# MCU_USB.net
KiCad netlist of a schematic drawn in Altium Designer
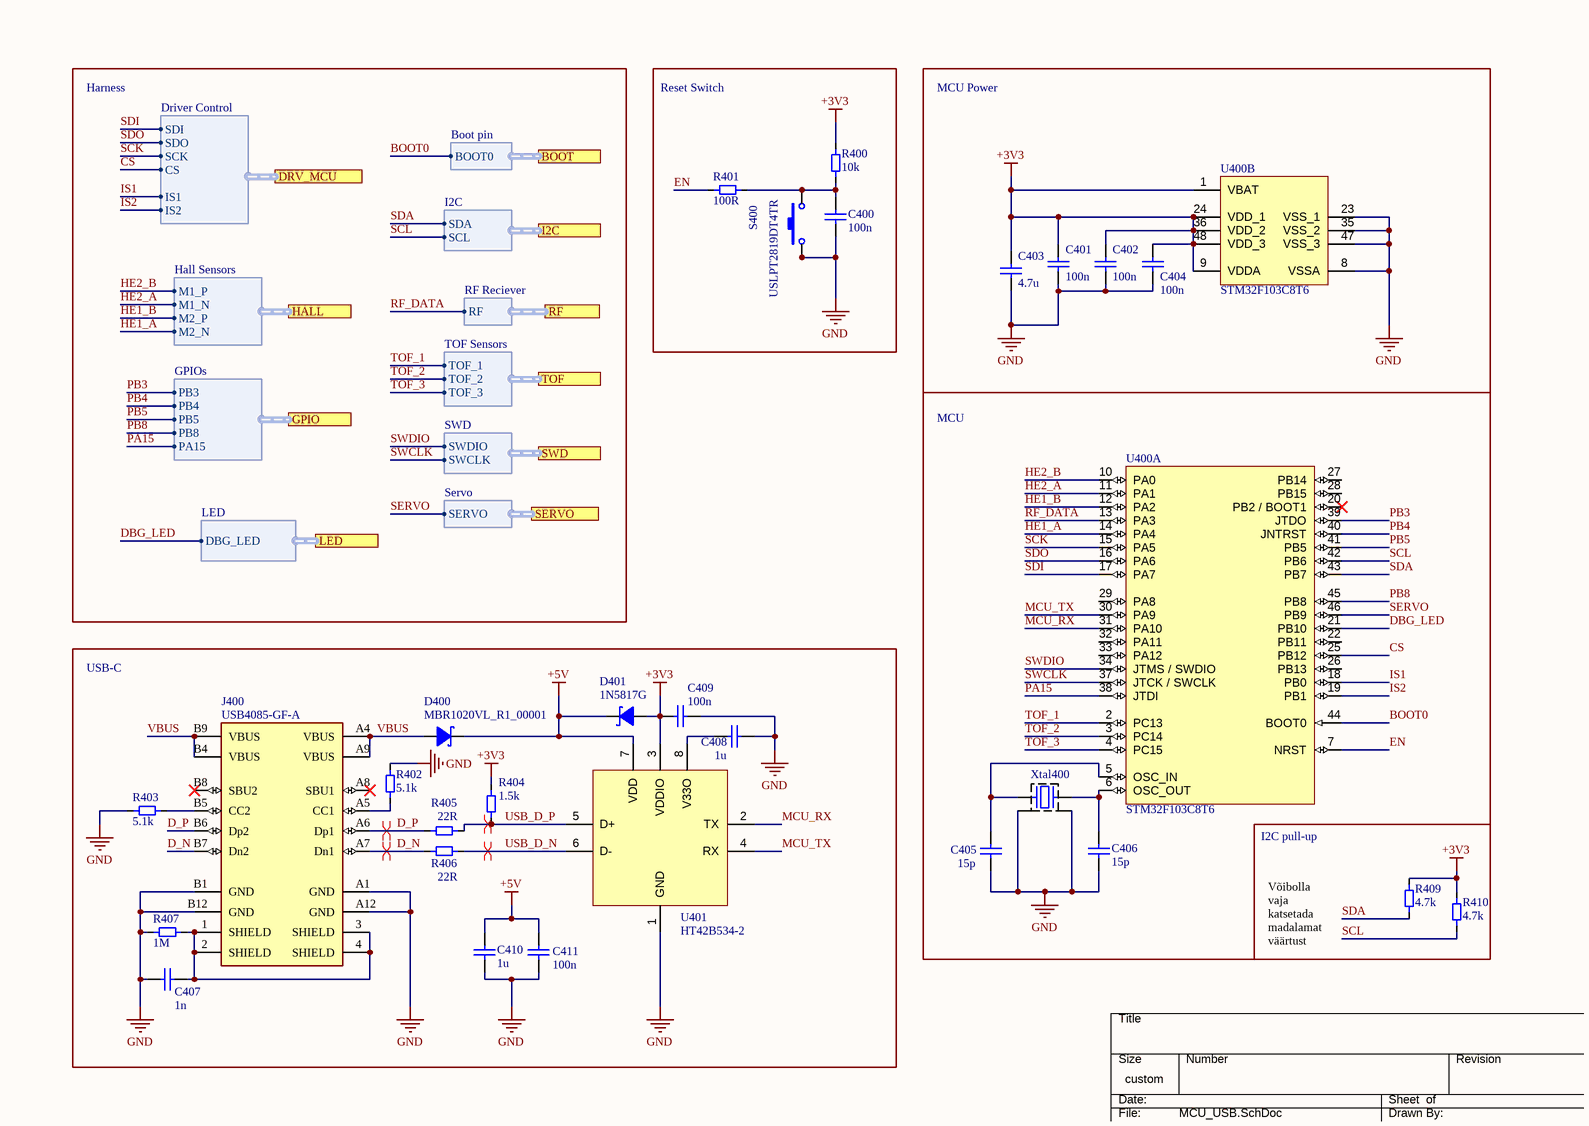
[diagram p0: MCU_USB.SchDoc]

(export (version "E")
  (design (tool "Eeschema 10.0.6"))
  (components
    (comp (ref "C400")
      (value "100n")
      (footprint "MLCC_0603_M")
      (description "MLCC, 0603, 100n, 10%, 50V, X7R")
      (fields (field (name "VOLTAGE") "50V") (field (name "TOLERANCE") "10%"))
      (libsource (lib "Krakul Vault") (part "CAPACITOR_NONPOL_IEC"))
    )
    (comp (ref "C401")
      (value "100n")
      (footprint "MLCC_0603_M")
      (description "MLCC, 0603, 100n, 10%, 50V, X7R")
      (fields (field (name "VOLTAGE") "50V") (field (name "TOLERANCE") "10%"))
      (libsource (lib "Krakul Vault") (part "CAPACITOR_NONPOL_IEC"))
    )
    (comp (ref "C402")
      (value "100n")
      (footprint "MLCC_0603_M")
      (description "MLCC, 0603, 100n, 10%, 50V, X7R")
      (fields (field (name "VOLTAGE") "50V") (field (name "TOLERANCE") "10%"))
      (libsource (lib "Krakul Vault") (part "CAPACITOR_NONPOL_IEC"))
    )
    (comp (ref "C403")
      (value "4.7u")
      (footprint "MLCC_0805_M")
      (description "MLCC, 0805, 4.7u, 20%, 50V, X5R")
      (fields (field (name "MANUFACTURER") "Any") (field (name "VOLTAGE") "50V"))
      (libsource (lib "Krakul Vault") (part "CAPACITOR_NONPOL_IEC"))
    )
    (comp (ref "C404")
      (value "100n")
      (footprint "MLCC_0603_M")
      (description "MLCC, 0603, 100n, 10%, 50V, X7R")
      (fields (field (name "VOLTAGE") "50V") (field (name "TOLERANCE") "10%"))
      (libsource (lib "Krakul Vault") (part "CAPACITOR_NONPOL_IEC"))
    )
    (comp (ref "C405")
      (value "15p")
      (footprint "MLCC_0402_M")
      (description "MLCC, 0402, 15p, 10%, 25V, C0G/NP0")
      (fields (field (name "MANUFACTURER") "Any") (field (name "TOLERANCE") "10%"))
      (libsource (lib "Krakul Vault") (part "CAPACITOR_NONPOL_IEC"))
    )
    (comp (ref "C406")
      (value "15p")
      (footprint "MLCC_0402_M")
      (description "MLCC, 0402, 15p, 10%, 25V, C0G/NP0")
      (fields (field (name "MANUFACTURER") "Any") (field (name "TOLERANCE") "10%"))
      (libsource (lib "Krakul Vault") (part "CAPACITOR_NONPOL_IEC"))
    )
    (comp (ref "C407")
      (value "1n")
      (footprint "MLCC_0603_M")
      (description "MLCC, 0603, 1n, 10%, 50V, X5R")
      (fields (field (name "MANUFACTURER") "Any") (field (name "TOLERANCE") "10%"))
      (libsource (lib "Krakul Vault") (part "CAPACITOR_NONPOL_IEC"))
    )
    (comp (ref "C408")
      (value "1u")
      (footprint "MLCC_0603_M")
      (description "MLCC, 0603, 1u, 10%, 50V, X5R")
      (fields (field (name "MANUFACTURER") "Any") (field (name "VOLTAGE") "50V"))
      (libsource (lib "Krakul Vault") (part "CAPACITOR_NONPOL_IEC"))
    )
    (comp (ref "C409")
      (value "100n")
      (footprint "MLCC_0603_M")
      (description "MLCC, 0603, 100n, 10%, 50V, X7R")
      (fields (field (name "VOLTAGE") "50V") (field (name "TOLERANCE") "10%"))
      (libsource (lib "Krakul Vault") (part "CAPACITOR_NONPOL_IEC"))
    )
    (comp (ref "C410")
      (value "1u")
      (footprint "MLCC_0603_M")
      (description "MLCC, 0603, 1u, 10%, 50V, X5R")
      (fields (field (name "MANUFACTURER") "Any") (field (name "VOLTAGE") "50V"))
      (libsource (lib "Krakul Vault") (part "CAPACITOR_NONPOL_IEC"))
    )
    (comp (ref "C411")
      (value "100n")
      (footprint "MLCC_0603_M")
      (description "MLCC, 0603, 100n, 10%, 50V, X7R")
      (fields (field (name "VOLTAGE") "50V") (field (name "TOLERANCE") "10%"))
      (libsource (lib "Krakul Vault") (part "CAPACITOR_NONPOL_IEC"))
    )
    (comp (ref "D400")
      (value "MBR1020VL_R1_00001")
      (footprint "FP-MBR1020VL_R1_00001-MFG")
      (description "Rectifier Diode, Schottky, 1 Phase, 1 Element, 1A, 20V V(RRM), Silicon")
      (fields (field (name "MANUFACTURER") "Panjit"))
      (libsource (lib "Krakul Vault") (part "Schottky generic 2 pins"))
    )
    (comp (ref "D401")
      (value "1N5817G")
      (footprint "SOD-323 based on 1N5817WS")
      (description "Rectifier Diode, Schottky, 1 Phase, 1 Element, 1A, 20V V(RRM), Silicon, DO-204AL")
      (fields (field (name "MANUFACTURER") "TWGMC / onsemi") (field (name "PART NUMBER") "1N5817WS"))
      (libsource (lib "Krakul Vault") (part "Schottky generic 2 pins"))
    )
    (comp (ref "J400")
      (value "USB4085-GF-A")
      (footprint "FP-USB4085-GF-A-MFG")
      (description "USB Connector, 16 Contact(s), Female, Right Angle, Solder Terminal, Locking, Receptacle")
      (fields (field (name "MANUFACTURER") "GCT") (field (name "PART NUMBER") "USB4800-03-A"))
      (libsource (lib "Krakul Vault") (part "USB4085-GF-A"))
    )
    (comp (ref "R400")
      (value "10k")
      (footprint "Resistor_0603_M")
      (description "Resistor, 0603, 10k, 1%, 1/10W")
      (fields (field (name "MANUFACTURER") "Any") (field (name "TOLERANCE") "1%"))
      (libsource (lib "Krakul Vault") (part "RESISTOR_GENERIC_IEC"))
    )
    (comp (ref "R401")
      (value "100R")
      (footprint "Resistor_0603_M")
      (description "Resistor, 0603, 100R, 1%, 1/10W")
      (fields (field (name "POWER") "100mW") (field (name "MANUFACTURER") "Any"))
      (libsource (lib "Krakul Vault") (part "RESISTOR_GENERIC_IEC"))
    )
    (comp (ref "R402")
      (value "5.1k")
      (footprint "Resistor_0603_M")
      (description "Resistor, 0603, 5.1k, 1%, 1/10W")
      (fields (field (name "POWER") "100mW") (field (name "MANUFACTURER") "Any"))
      (libsource (lib "Krakul Vault") (part "RESISTOR_GENERIC_IEC"))
    )
    (comp (ref "R403")
      (value "5.1k")
      (footprint "Resistor_0603_M")
      (description "Resistor, 0603, 5.1k, 1%, 1/10W")
      (fields (field (name "POWER") "100mW") (field (name "MANUFACTURER") "Any"))
      (libsource (lib "Krakul Vault") (part "RESISTOR_GENERIC_IEC"))
    )
    (comp (ref "R404")
      (value "1.5k")
      (footprint "Resistor_0603_M")
      (description "Resistor, 0603, 1.5k, 1%, 1/10W")
      (fields (field (name "MANUFACTURER") "Any") (field (name "POWER") "100mW"))
      (libsource (lib "Krakul Vault") (part "RESISTOR_GENERIC_IEC"))
    )
    (comp (ref "R405")
      (value "22R")
      (footprint "Resistor_0603_M")
      (description "Resistor, 0603, 22R, 1%, 1/10W")
      (fields (field (name "TOLERANCE") "1%") (field (name "MANUFACTURER") "Any"))
      (libsource (lib "Krakul Vault") (part "RESISTOR_GENERIC_IEC"))
    )
    (comp (ref "R406")
      (value "22R")
      (footprint "Resistor_0603_M")
      (description "Resistor, 0603, 22R, 1%, 1/10W")
      (fields (field (name "TOLERANCE") "1%") (field (name "MANUFACTURER") "Any"))
      (libsource (lib "Krakul Vault") (part "RESISTOR_GENERIC_IEC"))
    )
    (comp (ref "R407")
      (value "1M")
      (footprint "Resistor_1206_M")
      (description "Resistor, 1206, 1M, 1%, 1/4W")
      (fields (field (name "MANUFACTURER") "Any"))
      (libsource (lib "Krakul Vault") (part "RESISTOR_GENERIC_IEC"))
    )
    (comp (ref "R409")
      (value "4.7k")
      (footprint "Resistor_0603_M")
      (description "Resistor, 0603, 4.7k, 1%, 1/10W")
      (fields (field (name "MANUFACTURER") "Any") (field (name "POWER") "100mW"))
      (libsource (lib "Krakul Vault") (part "RESISTOR_GENERIC_IEC"))
    )
    (comp (ref "R410")
      (value "4.7k")
      (footprint "Resistor_0603_M")
      (description "Resistor, 0603, 4.7k, 1%, 1/10W")
      (fields (field (name "MANUFACTURER") "Any") (field (name "POWER") "100mW"))
      (libsource (lib "Krakul Vault") (part "RESISTOR_GENERIC_IEC"))
    )
    (comp (ref "S400")
      (value "USLPT2819DT4TR")
      (footprint "USLPT2819DT4TR-Footprint-1")
      (description "Keypad Switch, SPST, 0.05A, 1.96N, Solder Terminal, Panel Mount")
      (fields (field (name "MANUFACTURER") "TE Connectivity ALCOSWITCH Switches"))
      (libsource (lib "Krakul Vault") (part "Copy of Switch 4-pin"))
    )
    (comp (ref "U400")
      (value "STM32F103C8T6")
      (footprint "STM-LQFP48_M")
      (description "MCU 32-bit STM32F1 ARM Cortex M3 RISC 64KB Flash 2.5V/3.3V 48-Pin LQFP Tray")
      (fields (field (name "MANUFACTURER") "STMicroelectronics"))
      (libsource (lib "") (part "MC-ARM-STM32F103X4_6-SQ48_1"))
    )
    (comp (ref "U401")
      (value "HT42B534-2")
      (footprint "SOP-8 150mil")
      (description "USB to UART 3Mbps USB 2.0 SOP-8 Interface Controllers RoHS")
      (fields (field (name "MANUFACTURER") "HOLTEK"))
      (libsource (lib "Krakul Vault") (part "HT42B534-2"))
    )
    (comp (ref "Xtal400")
      (value "ABM11-16.000MHZ-12-N1G-T")
      (footprint "FP-ABM11-MFG")
      (description "Crystal 16MHz ±10ppm (Tol) ±15ppm (Stability) 12pF FUND 150Ohm 4-Pin Ultra Mini-CSMD T/R")
      (fields (field (name "MANUFACTURER") "Abracon LLC") (field (name "TOLERANCE") "0.001%"))
      (libsource (lib "Krakul Vault") (part "Crystal 4 pins"))
    )
  )
  (nets
    (net (code "15") (name "+3V3") (class "Default")
      (node (ref "C401") (pin "1") (pinfunction "1_1") (pintype "passive"))
      (node (ref "C402") (pin "1") (pinfunction "1_1") (pintype "passive"))
      (node (ref "C403") (pin "2") (pinfunction "2_2") (pintype "passive"))
      (node (ref "C404") (pin "1") (pinfunction "1_1") (pintype "passive"))
      (node (ref "C409") (pin "1") (pinfunction "1_1") (pintype "passive"))
      (node (ref "D401") (pin "2") (pinfunction "A_2") (pintype "passive"))
      (node (ref "R400") (pin "2") (pinfunction "2_2") (pintype "passive"))
      (node (ref "R404") (pin "2") (pinfunction "2_2") (pintype "passive"))
      (node (ref "R409") (pin "2") (pinfunction "2_2") (pintype "passive"))
      (node (ref "R410") (pin "2") (pinfunction "2_2") (pintype "passive"))
      (node (ref "U400") (pin "1") (pinfunction "VBAT_1") (pintype "power_in"))
      (node (ref "U400") (pin "24") (pinfunction "VDD_1_24") (pintype "power_in"))
      (node (ref "U400") (pin "36") (pinfunction "VDD_2_36") (pintype "power_in"))
      (node (ref "U400") (pin "48") (pinfunction "VDD_3_48") (pintype "power_in"))
      (node (ref "U400") (pin "9") (pinfunction "VDDA_9") (pintype "power_in"))
      (node (ref "U401") (pin "3") (pinfunction "VDDIO_3") (pintype "passive"))
    )
    (net (code "16") (name "+5V") (class "Default")
      (node (ref "C410") (pin "2") (pinfunction "2_2") (pintype "passive"))
      (node (ref "C411") (pin "1") (pinfunction "1_1") (pintype "passive"))
      (node (ref "D400") (pin "1") (pinfunction "C_1") (pintype "passive"))
      (node (ref "D401") (pin "1") (pinfunction "C_1") (pintype "passive"))
      (node (ref "U401") (pin "7") (pinfunction "VDD_7") (pintype "passive"))
    )
    (net (code "17") (name "/BOOT0") (class "Default")
      (node (ref "U400") (pin "44") (pinfunction "BOOT0_44") (pintype "input"))
    )
    (net (code "18") (name "/CS") (class "Default")
      (node (ref "U400") (pin "25") (pinfunction "PB12_25") (pintype "bidirectional"))
    )
    (net (code "19") (name "/DBG_LED") (class "Default")
      (node (ref "U400") (pin "21") (pinfunction "PB10_21") (pintype "bidirectional"))
    )
    (net (code "20") (name "/D_N") (class "Default")
      (node (ref "J400") (pin "A7") (pinfunction "Dn1_A7") (pintype "bidirectional"))
      (node (ref "J400") (pin "B7") (pinfunction "Dn2_B7") (pintype "bidirectional"))
      (node (ref "R406") (pin "1") (pinfunction "1_1") (pintype "passive"))
    )
    (net (code "21") (name "/D_P") (class "Default")
      (node (ref "J400") (pin "A6") (pinfunction "Dp1_A6") (pintype "bidirectional"))
      (node (ref "J400") (pin "B6") (pinfunction "Dp2_B6") (pintype "bidirectional"))
      (node (ref "R405") (pin "1") (pinfunction "1_1") (pintype "passive"))
    )
    (net (code "22") (name "/EN") (class "Default")
      (node (ref "R401") (pin "2") (pinfunction "2_2") (pintype "passive"))
      (node (ref "U400") (pin "7") (pinfunction "NRST_7") (pintype "bidirectional"))
    )
    (net (code "23") (name "/HE1_A") (class "Default")
      (node (ref "U400") (pin "14") (pinfunction "PA4_14") (pintype "bidirectional"))
    )
    (net (code "24") (name "/HE1_B") (class "Default")
      (node (ref "U400") (pin "12") (pinfunction "PA2_12") (pintype "bidirectional"))
    )
    (net (code "25") (name "/HE2_A") (class "Default")
      (node (ref "U400") (pin "11") (pinfunction "PA1_11") (pintype "bidirectional"))
    )
    (net (code "26") (name "/HE2_B") (class "Default")
      (node (ref "U400") (pin "10") (pinfunction "PA0_10") (pintype "bidirectional"))
    )
    (net (code "27") (name "/IS1") (class "Default")
      (node (ref "U400") (pin "18") (pinfunction "PB0_18") (pintype "bidirectional"))
    )
    (net (code "28") (name "/IS2") (class "Default")
      (node (ref "U400") (pin "19") (pinfunction "PB1_19") (pintype "bidirectional"))
    )
    (net (code "29") (name "/MCU_RX") (class "Default")
      (node (ref "U400") (pin "31") (pinfunction "PA10_31") (pintype "bidirectional"))
      (node (ref "U401") (pin "2") (pinfunction "TX_2") (pintype "passive"))
    )
    (net (code "30") (name "/MCU_TX") (class "Default")
      (node (ref "U400") (pin "30") (pinfunction "PA9_30") (pintype "bidirectional"))
      (node (ref "U401") (pin "4") (pinfunction "RX_4") (pintype "passive"))
    )
    (net (code "31") (name "/PA15") (class "Default")
      (node (ref "U400") (pin "38") (pinfunction "JTDI_38") (pintype "bidirectional"))
    )
    (net (code "32") (name "/PB3") (class "Default")
      (node (ref "U400") (pin "39") (pinfunction "JTDO_39") (pintype "bidirectional"))
    )
    (net (code "33") (name "/PB4") (class "Default")
      (node (ref "U400") (pin "40") (pinfunction "JNTRST_40") (pintype "bidirectional"))
    )
    (net (code "34") (name "/PB5") (class "Default")
      (node (ref "U400") (pin "41") (pinfunction "PB5_41") (pintype "bidirectional"))
    )
    (net (code "35") (name "/PB8") (class "Default")
      (node (ref "U400") (pin "45") (pinfunction "PB8_45") (pintype "bidirectional"))
    )
    (net (code "36") (name "/RF_DATA") (class "Default")
      (node (ref "U400") (pin "13") (pinfunction "PA3_13") (pintype "bidirectional"))
    )
    (net (code "37") (name "/SCK") (class "Default")
      (node (ref "U400") (pin "15") (pinfunction "PA5_15") (pintype "bidirectional"))
    )
    (net (code "38") (name "/SCL") (class "Default")
      (node (ref "R410") (pin "1") (pinfunction "1_1") (pintype "passive"))
      (node (ref "U400") (pin "42") (pinfunction "PB6_42") (pintype "bidirectional"))
    )
    (net (code "39") (name "/SDA") (class "Default")
      (node (ref "R409") (pin "1") (pinfunction "1_1") (pintype "passive"))
      (node (ref "U400") (pin "43") (pinfunction "PB7_43") (pintype "bidirectional"))
    )
    (net (code "40") (name "/SDI") (class "Default")
      (node (ref "U400") (pin "17") (pinfunction "PA7_17") (pintype "bidirectional"))
    )
    (net (code "41") (name "/SDO") (class "Default")
      (node (ref "U400") (pin "16") (pinfunction "PA6_16") (pintype "bidirectional"))
    )
    (net (code "42") (name "/SERVO") (class "Default")
      (node (ref "U400") (pin "46") (pinfunction "PB9_46") (pintype "bidirectional"))
    )
    (net (code "43") (name "/SWCLK") (class "Default")
      (node (ref "U400") (pin "37") (pinfunction "JTCK_/_SWCLK_37") (pintype "bidirectional"))
    )
    (net (code "44") (name "/SWDIO") (class "Default")
      (node (ref "U400") (pin "34") (pinfunction "JTMS_/_SWDIO_34") (pintype "bidirectional"))
    )
    (net (code "45") (name "/TOF_1") (class "Default")
      (node (ref "U400") (pin "2") (pinfunction "PC13_2") (pintype "bidirectional"))
    )
    (net (code "46") (name "/TOF_2") (class "Default")
      (node (ref "U400") (pin "3") (pinfunction "PC14_3") (pintype "bidirectional"))
    )
    (net (code "47") (name "/TOF_3") (class "Default")
      (node (ref "U400") (pin "4") (pinfunction "PC15_4") (pintype "bidirectional"))
    )
    (net (code "48") (name "/USB_D_N") (class "Default")
      (node (ref "R406") (pin "2") (pinfunction "2_2") (pintype "passive"))
      (node (ref "U401") (pin "6") (pinfunction "D-_6") (pintype "passive"))
    )
    (net (code "49") (name "/USB_D_P") (class "Default")
      (node (ref "R404") (pin "1") (pinfunction "1_1") (pintype "passive"))
      (node (ref "R405") (pin "2") (pinfunction "2_2") (pintype "passive"))
      (node (ref "U401") (pin "5") (pinfunction "D+_5") (pintype "passive"))
    )
    (net (code "50") (name "/VBUS") (class "Default")
      (node (ref "D400") (pin "2") (pinfunction "A_2") (pintype "passive"))
      (node (ref "J400") (pin "A4") (pinfunction "VBUS_A4") (pintype "power_in"))
      (node (ref "J400") (pin "A9") (pinfunction "VBUS_A9") (pintype "power_in"))
      (node (ref "J400") (pin "B4") (pinfunction "VBUS_B4") (pintype "power_in"))
      (node (ref "J400") (pin "B9") (pinfunction "VBUS_B9") (pintype "power_in"))
    )
    (net (code "61") (name "GND") (class "Default")
      (node (ref "C400") (pin "1") (pinfunction "1_1") (pintype "passive"))
      (node (ref "C401") (pin "2") (pinfunction "2_2") (pintype "passive"))
      (node (ref "C402") (pin "2") (pinfunction "2_2") (pintype "passive"))
      (node (ref "C403") (pin "1") (pinfunction "1_1") (pintype "passive"))
      (node (ref "C404") (pin "2") (pinfunction "2_2") (pintype "passive"))
      (node (ref "C405") (pin "1") (pinfunction "1_1") (pintype "passive"))
      (node (ref "C406") (pin "1") (pinfunction "1_1") (pintype "passive"))
      (node (ref "C407") (pin "1") (pinfunction "1_1") (pintype "passive"))
      (node (ref "C408") (pin "2") (pinfunction "2_2") (pintype "passive"))
      (node (ref "C409") (pin "2") (pinfunction "2_2") (pintype "passive"))
      (node (ref "C410") (pin "1") (pinfunction "1_1") (pintype "passive"))
      (node (ref "C411") (pin "2") (pinfunction "2_2") (pintype "passive"))
      (node (ref "J400") (pin "A1") (pinfunction "GND_A1") (pintype "power_in"))
      (node (ref "J400") (pin "A12") (pinfunction "GND_A12") (pintype "power_in"))
      (node (ref "J400") (pin "B1") (pinfunction "GND_B1") (pintype "power_in"))
      (node (ref "J400") (pin "B12") (pinfunction "GND_B12") (pintype "power_in"))
      (node (ref "R402") (pin "2") (pinfunction "2_2") (pintype "passive"))
      (node (ref "R403") (pin "1") (pinfunction "1_1") (pintype "passive"))
      (node (ref "R407") (pin "2") (pinfunction "2_2") (pintype "passive"))
      (node (ref "S400") (pin "1") (pinfunction "1_1") (pintype "passive"))
      (node (ref "S400") (pin "2") (pinfunction "2_2") (pintype "passive"))
      (node (ref "U400") (pin "23") (pinfunction "VSS_1_23") (pintype "power_in"))
      (node (ref "U400") (pin "35") (pinfunction "VSS_2_35") (pintype "power_in"))
      (node (ref "U400") (pin "47") (pinfunction "VSS_3_47") (pintype "power_in"))
      (node (ref "U400") (pin "8") (pinfunction "VSSA_8") (pintype "power_in"))
      (node (ref "U401") (pin "1") (pinfunction "GND_1") (pintype "passive"))
      (node (ref "Xtal400") (pin "2") (pinfunction "2_2") (pintype "power_in"))
      (node (ref "Xtal400") (pin "4") (pinfunction "4_4") (pintype "power_in"))
    )
    (net (code "62") (name "Net-(C400-Pad2)") (class "Default")
      (node (ref "C400") (pin "2") (pinfunction "2_2") (pintype "passive"))
      (node (ref "R400") (pin "1") (pinfunction "1_1") (pintype "passive"))
      (node (ref "R401") (pin "1") (pinfunction "1_1") (pintype "passive"))
      (node (ref "S400") (pin "3") (pinfunction "3_3") (pintype "passive"))
      (node (ref "S400") (pin "4") (pinfunction "4_4") (pintype "passive"))
    )
    (net (code "63") (name "Net-(C407-Pad2)") (class "Default")
      (node (ref "C407") (pin "2") (pinfunction "2_2") (pintype "passive"))
      (node (ref "J400") (pin "1") (pinfunction "SHIELD_1") (pintype "passive"))
      (node (ref "J400") (pin "2") (pinfunction "SHIELD_2") (pintype "passive"))
      (node (ref "J400") (pin "3") (pinfunction "SHIELD_3") (pintype "passive"))
      (node (ref "J400") (pin "4") (pinfunction "SHIELD_4") (pintype "passive"))
      (node (ref "R407") (pin "1") (pinfunction "1_1") (pintype "passive"))
    )
    (net (code "64") (name "Net-(J400-CC1)") (class "Default")
      (node (ref "J400") (pin "A5") (pinfunction "CC1_A5") (pintype "bidirectional"))
      (node (ref "R402") (pin "1") (pinfunction "1_1") (pintype "passive"))
    )
    (net (code "65") (name "Net-(J400-CC2)") (class "Default")
      (node (ref "J400") (pin "B5") (pinfunction "CC2_B5") (pintype "bidirectional"))
      (node (ref "R403") (pin "2") (pinfunction "2_2") (pintype "passive"))
    )
    (net (code "66") (name "Net-(U400A-OSC_IN)") (class "Default")
      (node (ref "C405") (pin "2") (pinfunction "2_2") (pintype "passive"))
      (node (ref "U400") (pin "5") (pinfunction "OSC_IN_5") (pintype "bidirectional"))
      (node (ref "Xtal400") (pin "1") (pinfunction "1_1") (pintype "passive"))
    )
    (net (code "67") (name "Net-(U400A-OSC_OUT)") (class "Default")
      (node (ref "C406") (pin "2") (pinfunction "2_2") (pintype "passive"))
      (node (ref "U400") (pin "6") (pinfunction "OSC_OUT_6") (pintype "bidirectional"))
      (node (ref "Xtal400") (pin "3") (pinfunction "3_3") (pintype "passive"))
    )
    (net (code "68") (name "Net-(U401-V33O)") (class "Default")
      (node (ref "C408") (pin "1") (pinfunction "1_1") (pintype "passive"))
      (node (ref "U401") (pin "8") (pinfunction "V33O_8") (pintype "passive"))
    )
    (net (code "69") (name "unconnected-(J400-SBU1-PadA8)") (class "Default")
      (node (ref "J400") (pin "A8") (pinfunction "SBU1_A8") (pintype "bidirectional+no_connect"))
    )
    (net (code "70") (name "unconnected-(J400-SBU2-PadB8)") (class "Default")
      (node (ref "J400") (pin "B8") (pinfunction "SBU2_B8") (pintype "bidirectional+no_connect"))
    )
    (net (code "71") (name "unconnected-(U400A-PA8-Pad29)") (class "Default")
      (node (ref "U400") (pin "29") (pinfunction "PA8_29") (pintype "bidirectional"))
    )
    (net (code "72") (name "unconnected-(U400A-PA11-Pad32)") (class "Default")
      (node (ref "U400") (pin "32") (pinfunction "PA11_32") (pintype "bidirectional"))
    )
    (net (code "73") (name "unconnected-(U400A-PA12-Pad33)") (class "Default")
      (node (ref "U400") (pin "33") (pinfunction "PA12_33") (pintype "bidirectional"))
    )
    (net (code "74") (name "unconnected-(U400A-PB2_{slash}_BOOT1-Pad20)") (class "Default")
      (node (ref "U400") (pin "20") (pinfunction "PB2_/_BOOT1_20") (pintype "bidirectional+no_connect"))
    )
    (net (code "75") (name "unconnected-(U400A-PB11-Pad22)") (class "Default")
      (node (ref "U400") (pin "22") (pinfunction "PB11_22") (pintype "bidirectional"))
    )
    (net (code "76") (name "unconnected-(U400A-PB13-Pad26)") (class "Default")
      (node (ref "U400") (pin "26") (pinfunction "PB13_26") (pintype "bidirectional"))
    )
    (net (code "77") (name "unconnected-(U400A-PB14-Pad27)") (class "Default")
      (node (ref "U400") (pin "27") (pinfunction "PB14_27") (pintype "bidirectional"))
    )
    (net (code "78") (name "unconnected-(U400A-PB15-Pad28)") (class "Default")
      (node (ref "U400") (pin "28") (pinfunction "PB15_28") (pintype "bidirectional"))
    )
  )
)
